# 08_BESIDE_CPU.net
KiCad netlist of a schematic drawn in Altium Designer
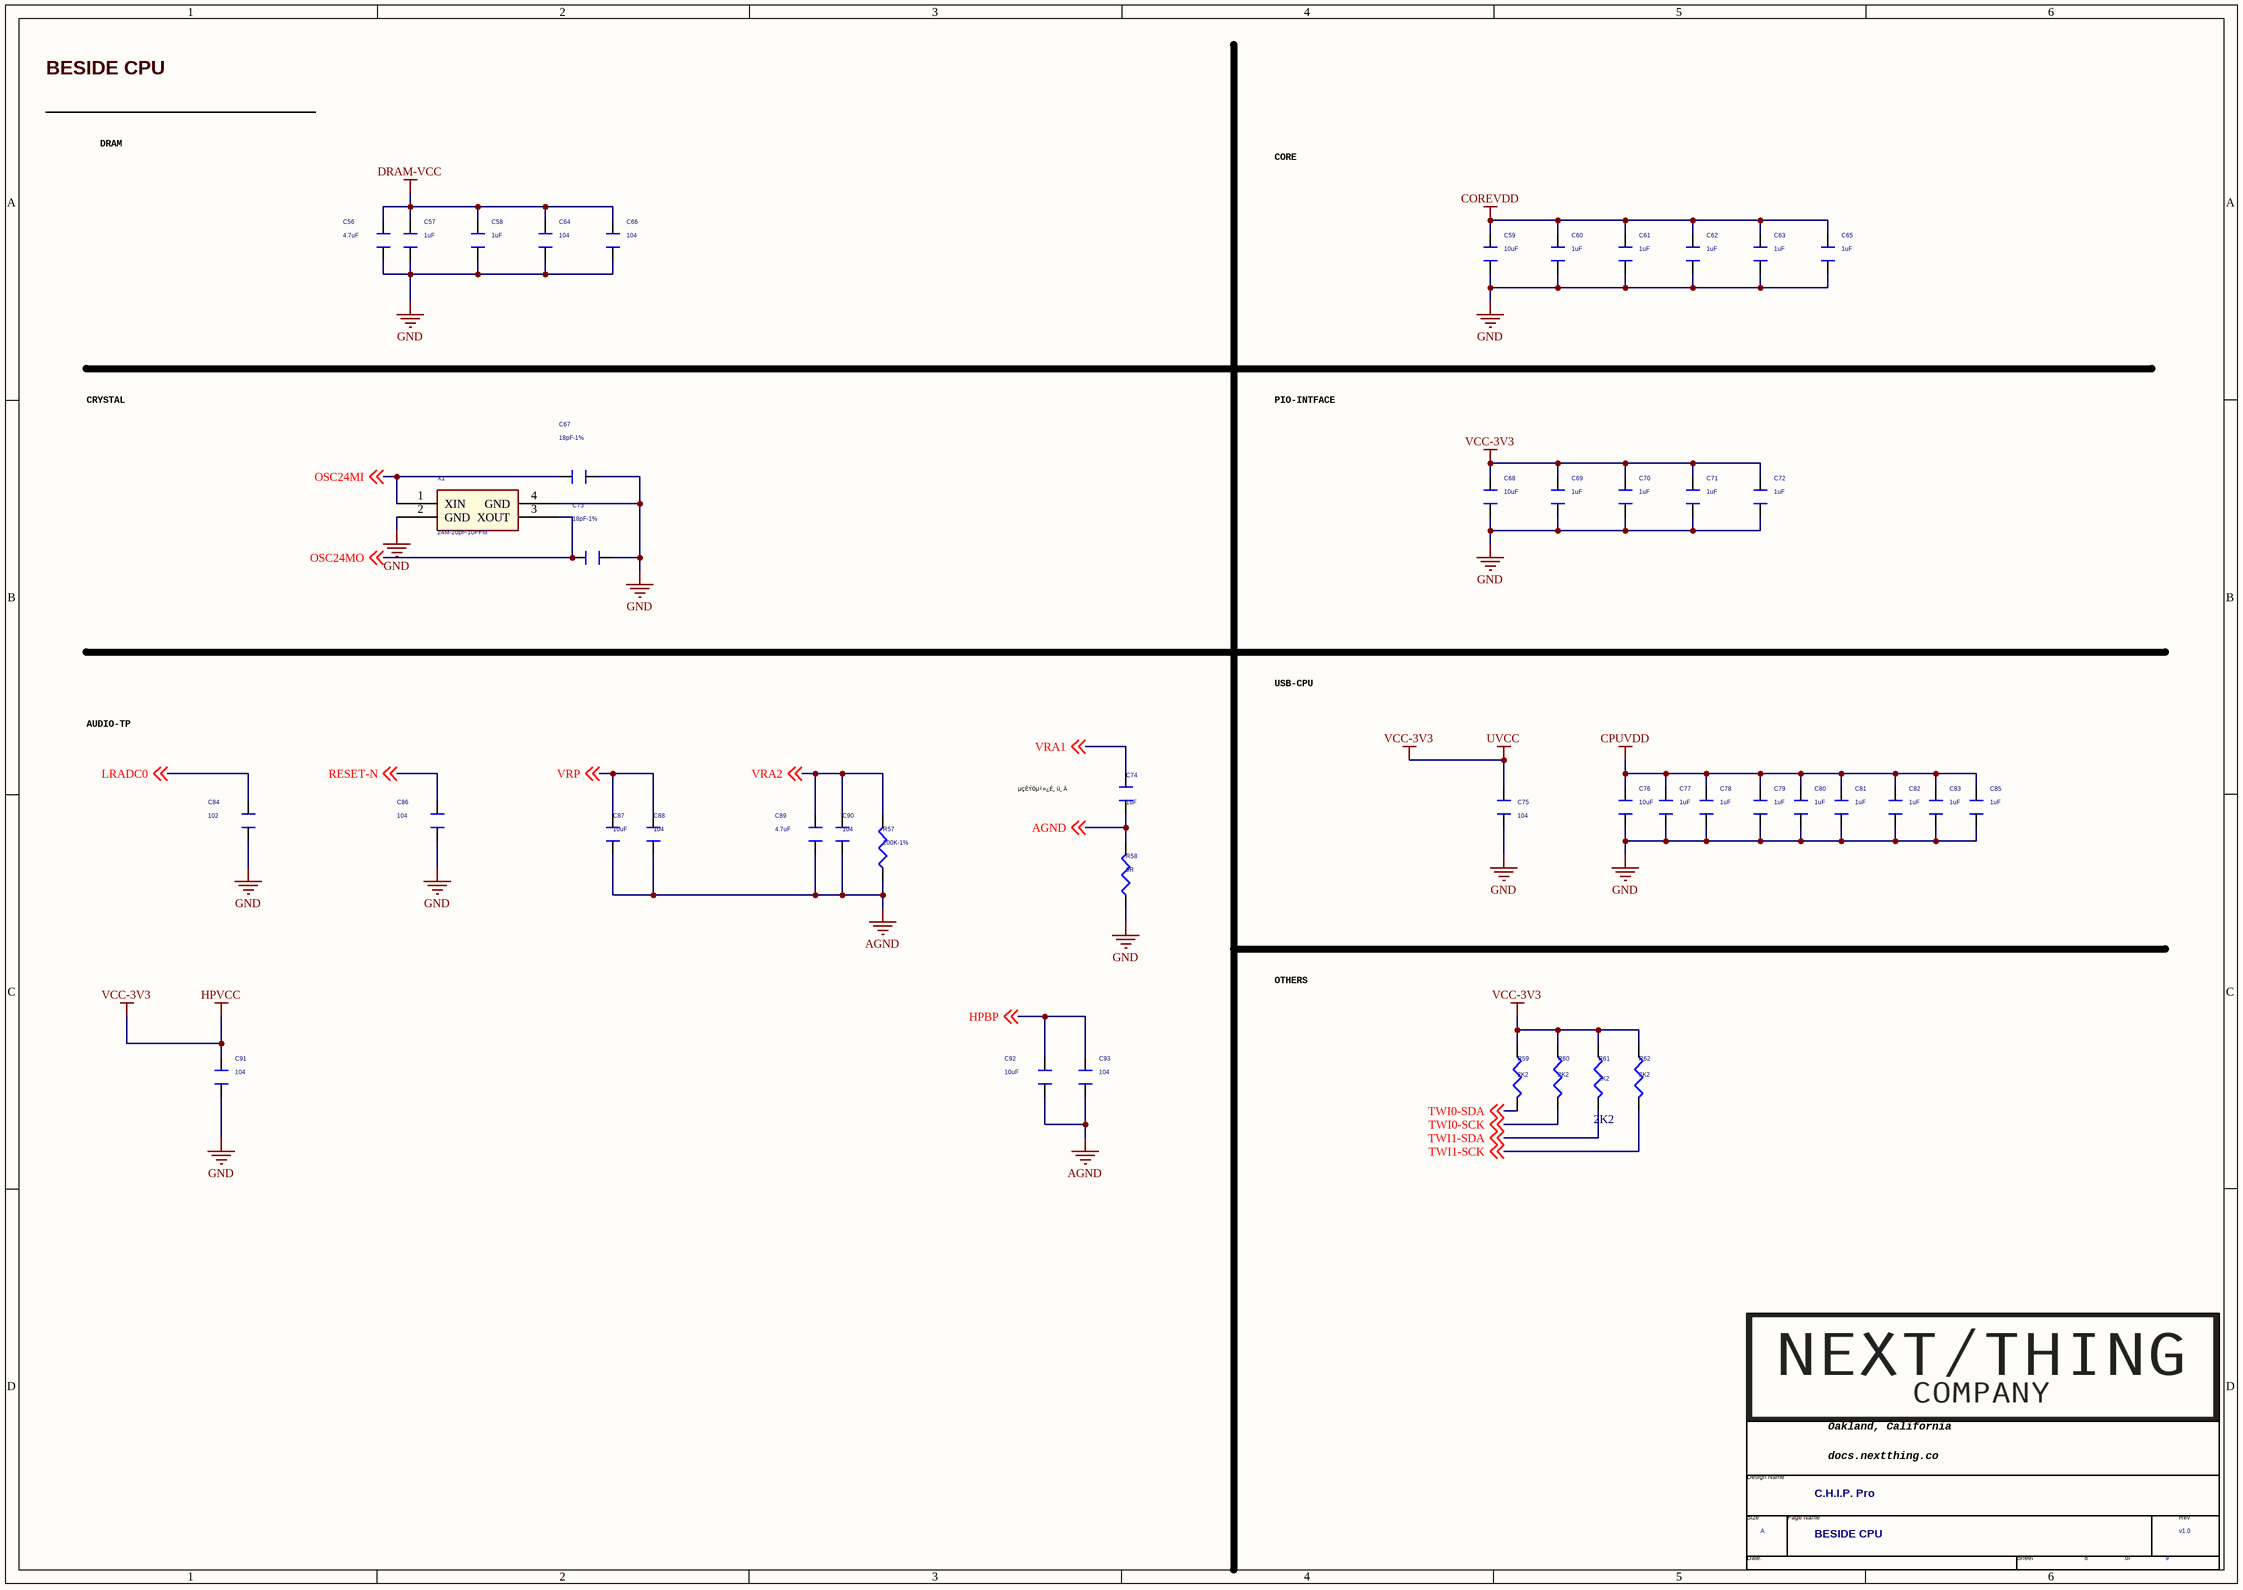
[diagram p0: 08 BESIDE CPU.SchDoc]

(export (version "E")
  (design (tool "Eeschema 10.0.6"))
  (components
    (comp (ref "C56") (value "4.7uF") (footprint "C0603") (libsource (lib "*") (part "CAPACITOR_0_Dup4")))
    (comp (ref "C57") (value "1uF") (footprint "C0402") (libsource (lib "*") (part "CAPACITOR_0_Dup4")))
    (comp (ref "C58") (value "1uF") (footprint "C0402") (libsource (lib "*") (part "CAPACITOR_0_Dup4")))
    (comp (ref "C59") (value "10uF") (footprint "C0603") (libsource (lib "*") (part "CAPACITOR_0_Dup3")))
    (comp (ref "C60") (value "1uF") (footprint "C0402") (libsource (lib "*") (part "CAPACITOR_0_Dup3")))
    (comp (ref "C61") (value "1uF") (footprint "C0402") (libsource (lib "*") (part "CAPACITOR_0_Dup3")))
    (comp (ref "C62") (value "1uF") (footprint "C0402") (libsource (lib "*") (part "CAPACITOR_0_Dup3")))
    (comp (ref "C63") (value "1uF") (footprint "C0402") (libsource (lib "*") (part "CAPACITOR_0_Dup3")))
    (comp (ref "C64") (value "104") (footprint "C0201") (libsource (lib "*") (part "CAPACITOR_0_Dup4")))
    (comp (ref "C65") (value "1uF") (footprint "C0402") (libsource (lib "*") (part "CAPACITOR_0_Dup3")))
    (comp (ref "C66") (value "104") (footprint "C0201") (libsource (lib "*") (part "CAPACITOR_0_Dup4")))
    (comp (ref "C67") (value "18pF-1%") (footprint "C0201") (libsource (lib "*") (part "CAPACITOR_0_Dup4")))
    (comp (ref "C68") (value "10uF") (footprint "C0603") (libsource (lib "*") (part "CAPACITOR_0_Dup3")))
    (comp (ref "C69") (value "1uF") (footprint "C0402") (libsource (lib "*") (part "CAPACITOR_0_Dup4")))
    (comp (ref "C70") (value "1uF") (footprint "C0402") (libsource (lib "*") (part "CAPACITOR_0_Dup4")))
    (comp (ref "C71") (value "1uF") (footprint "C0402") (libsource (lib "*") (part "CAPACITOR_0_Dup4")))
    (comp (ref "C72") (value "1uF") (footprint "C0402") (libsource (lib "*") (part "CAPACITOR_0_Dup4")))
    (comp (ref "C73") (value "18pF-1%") (footprint "C0201") (libsource (lib "*") (part "CAPACITOR_0_Dup4")))
    (comp (ref "C74") (value "1uF") (footprint "C0402") (libsource (lib "*") (part "CAPACITOR_0_Dup4")))
    (comp (ref "C75") (value "104") (footprint "C0201") (libsource (lib "*") (part "CAPACITOR_0_Dup4")))
    (comp (ref "C76") (value "10uF") (footprint "C0603") (libsource (lib "*") (part "CAPACITOR_0_Dup3")))
    (comp (ref "C77") (value "1uF") (footprint "C0402") (libsource (lib "*") (part "CAPACITOR_0_Dup3")))
    (comp (ref "C78") (value "1uF") (footprint "C0402") (libsource (lib "*") (part "CAPACITOR_0_Dup3")))
    (comp (ref "C79") (value "1uF") (footprint "C0402") (libsource (lib "*") (part "CAPACITOR_0_Dup3")))
    (comp (ref "C80") (value "1uF") (footprint "C0402") (libsource (lib "*") (part "CAPACITOR_0_Dup3")))
    (comp (ref "C81") (value "1uF") (footprint "C0402") (libsource (lib "*") (part "CAPACITOR_0_Dup3")))
    (comp (ref "C82") (value "1uF") (footprint "C0402") (libsource (lib "*") (part "CAPACITOR_0_Dup3")))
    (comp (ref "C83") (value "1uF") (footprint "C0402") (libsource (lib "*") (part "CAPACITOR_0_Dup3")))
    (comp (ref "C84") (value "102") (footprint "C0201") (libsource (lib "*") (part "CAPACITOR_0_Dup4")))
    (comp (ref "C85") (value "1uF") (footprint "C0402") (libsource (lib "*") (part "CAPACITOR_0_Dup3")))
    (comp (ref "C86") (value "104") (footprint "C0201") (libsource (lib "*") (part "CAPACITOR_0_Dup4")))
    (comp (ref "C87") (value "10uF") (footprint "C0603") (libsource (lib "*") (part "CAPACITOR_0_Dup4")))
    (comp (ref "C88") (value "104") (footprint "C0201") (libsource (lib "*") (part "CAPACITOR_0_Dup4")))
    (comp (ref "C89") (value "4.7uF") (footprint "C0603") (libsource (lib "*") (part "CAPACITOR_0_Dup4")))
    (comp (ref "C90") (value "104") (footprint "C0201") (libsource (lib "*") (part "CAPACITOR_0_Dup4")))
    (comp (ref "C91") (value "104") (footprint "C0201") (libsource (lib "*") (part "CAPACITOR_0_Dup4")))
    (comp (ref "C92") (value "10uF") (footprint "C0603") (libsource (lib "*") (part "CAPACITOR_0_Dup4")))
    (comp (ref "C93") (value "104") (footprint "C0201") (libsource (lib "*") (part "CAPACITOR_0_Dup4")))
    (comp (ref "R57") (value "200K-1%") (footprint "R0201") (libsource (lib "*") (part "R_Dup2")))
    (comp (ref "R58") (value "0R") (footprint "R0201") (libsource (lib "*") (part "R_Dup2")))
    (comp (ref "R59") (value "2K2") (footprint "R0201") (libsource (lib "*") (part "R_Dup2")))
    (comp (ref "R60") (value "2K2") (footprint "R0201") (libsource (lib "*") (part "R_Dup2")))
    (comp (ref "R61")
      (value "2K2")
      (footprint "R0201")
      (fields (field (name "ALTIUM_VALUE") "2K2"))
      (libsource (lib "*") (part "R_Dup2"))
    )
    (comp (ref "R62") (value "2K2") (footprint "R0201") (libsource (lib "*") (part "R_Dup2")))
    (comp (ref "X1")
      (value "24M-20pF-10PPM")
      (footprint "CRY-3225")
      (description "Crystal 24MHz 20pF 10ppm  -30 to +85")
      (fields (field (name "PART NUMBER") "7M24000004"))
      (libsource (lib "*") (part "CRYSTAL-4_3"))
    )
  )
  (nets
    (net (code "1") (name "AGND") (class "Default")
      (node (ref "C74") (pin "1") (pinfunction "1_1") (pintype "passive"))
      (node (ref "C87") (pin "1") (pinfunction "1_1") (pintype "passive"))
      (node (ref "C88") (pin "1") (pinfunction "1_1") (pintype "passive"))
      (node (ref "C89") (pin "1") (pinfunction "1_1") (pintype "passive"))
      (node (ref "C90") (pin "1") (pinfunction "1_1") (pintype "passive"))
      (node (ref "C92") (pin "1") (pinfunction "1_1") (pintype "passive"))
      (node (ref "C93") (pin "1") (pinfunction "1_1") (pintype "passive"))
      (node (ref "R57") (pin "1") (pinfunction "1_1") (pintype "passive"))
      (node (ref "R58") (pin "2") (pinfunction "2_2") (pintype "passive"))
    )
    (net (code "2") (name "COREVDD") (class "Default")
      (node (ref "C59") (pin "1") (pinfunction "1_1") (pintype "passive"))
      (node (ref "C60") (pin "1") (pinfunction "1_1") (pintype "passive"))
      (node (ref "C61") (pin "1") (pinfunction "1_1") (pintype "passive"))
      (node (ref "C62") (pin "1") (pinfunction "1_1") (pintype "passive"))
      (node (ref "C63") (pin "1") (pinfunction "1_1") (pintype "passive"))
      (node (ref "C65") (pin "1") (pinfunction "1_1") (pintype "passive"))
    )
    (net (code "3") (name "CPUVDD") (class "Default")
      (node (ref "C76") (pin "1") (pinfunction "1_1") (pintype "passive"))
      (node (ref "C77") (pin "1") (pinfunction "1_1") (pintype "passive"))
      (node (ref "C78") (pin "1") (pinfunction "1_1") (pintype "passive"))
      (node (ref "C79") (pin "1") (pinfunction "1_1") (pintype "passive"))
      (node (ref "C80") (pin "1") (pinfunction "1_1") (pintype "passive"))
      (node (ref "C81") (pin "1") (pinfunction "1_1") (pintype "passive"))
      (node (ref "C82") (pin "1") (pinfunction "1_1") (pintype "passive"))
      (node (ref "C83") (pin "1") (pinfunction "1_1") (pintype "passive"))
      (node (ref "C85") (pin "1") (pinfunction "1_1") (pintype "passive"))
    )
    (net (code "4") (name "DRAM-VCC") (class "Default")
      (node (ref "C56") (pin "2") (pinfunction "2_2") (pintype "passive"))
      (node (ref "C57") (pin "2") (pinfunction "2_2") (pintype "passive"))
      (node (ref "C58") (pin "2") (pinfunction "2_2") (pintype "passive"))
      (node (ref "C64") (pin "2") (pinfunction "2_2") (pintype "passive"))
      (node (ref "C66") (pin "2") (pinfunction "2_2") (pintype "passive"))
    )
    (net (code "5") (name "GND") (class "Default")
      (node (ref "C56") (pin "1") (pinfunction "1_1") (pintype "passive"))
      (node (ref "C57") (pin "1") (pinfunction "1_1") (pintype "passive"))
      (node (ref "C58") (pin "1") (pinfunction "1_1") (pintype "passive"))
      (node (ref "C59") (pin "2") (pinfunction "2_2") (pintype "passive"))
      (node (ref "C60") (pin "2") (pinfunction "2_2") (pintype "passive"))
      (node (ref "C61") (pin "2") (pinfunction "2_2") (pintype "passive"))
      (node (ref "C62") (pin "2") (pinfunction "2_2") (pintype "passive"))
      (node (ref "C63") (pin "2") (pinfunction "2_2") (pintype "passive"))
      (node (ref "C64") (pin "1") (pinfunction "1_1") (pintype "passive"))
      (node (ref "C65") (pin "2") (pinfunction "2_2") (pintype "passive"))
      (node (ref "C66") (pin "1") (pinfunction "1_1") (pintype "passive"))
      (node (ref "C67") (pin "1") (pinfunction "1_1") (pintype "passive"))
      (node (ref "C68") (pin "2") (pinfunction "2_2") (pintype "passive"))
      (node (ref "C69") (pin "1") (pinfunction "1_1") (pintype "passive"))
      (node (ref "C70") (pin "1") (pinfunction "1_1") (pintype "passive"))
      (node (ref "C71") (pin "1") (pinfunction "1_1") (pintype "passive"))
      (node (ref "C72") (pin "1") (pinfunction "1_1") (pintype "passive"))
      (node (ref "C73") (pin "1") (pinfunction "1_1") (pintype "passive"))
      (node (ref "C75") (pin "1") (pinfunction "1_1") (pintype "passive"))
      (node (ref "C76") (pin "2") (pinfunction "2_2") (pintype "passive"))
      (node (ref "C77") (pin "2") (pinfunction "2_2") (pintype "passive"))
      (node (ref "C78") (pin "2") (pinfunction "2_2") (pintype "passive"))
      (node (ref "C79") (pin "2") (pinfunction "2_2") (pintype "passive"))
      (node (ref "C80") (pin "2") (pinfunction "2_2") (pintype "passive"))
      (node (ref "C81") (pin "2") (pinfunction "2_2") (pintype "passive"))
      (node (ref "C82") (pin "2") (pinfunction "2_2") (pintype "passive"))
      (node (ref "C83") (pin "2") (pinfunction "2_2") (pintype "passive"))
      (node (ref "C84") (pin "1") (pinfunction "1_1") (pintype "passive"))
      (node (ref "C85") (pin "2") (pinfunction "2_2") (pintype "passive"))
      (node (ref "C86") (pin "1") (pinfunction "1_1") (pintype "passive"))
      (node (ref "C91") (pin "1") (pinfunction "1_1") (pintype "passive"))
      (node (ref "R58") (pin "1") (pinfunction "1_1") (pintype "passive"))
      (node (ref "X1") (pin "2") (pinfunction "GND_2") (pintype "power_in"))
      (node (ref "X1") (pin "4") (pinfunction "GND_4") (pintype "power_in"))
    )
    (net (code "6") (name "HPBP") (class "Default")
      (node (ref "C92") (pin "2") (pinfunction "2_2") (pintype "passive"))
      (node (ref "C93") (pin "2") (pinfunction "2_2") (pintype "passive"))
    )
    (net (code "7") (name "HPVCC") (class "Default")
      (node (ref "C68") (pin "1") (pinfunction "1_1") (pintype "passive"))
      (node (ref "C69") (pin "2") (pinfunction "2_2") (pintype "passive"))
      (node (ref "C70") (pin "2") (pinfunction "2_2") (pintype "passive"))
      (node (ref "C71") (pin "2") (pinfunction "2_2") (pintype "passive"))
      (node (ref "C72") (pin "2") (pinfunction "2_2") (pintype "passive"))
      (node (ref "C75") (pin "2") (pinfunction "2_2") (pintype "passive"))
      (node (ref "C91") (pin "2") (pinfunction "2_2") (pintype "passive"))
      (node (ref "R59") (pin "1") (pinfunction "1_1") (pintype "passive"))
      (node (ref "R60") (pin "1") (pinfunction "1_1") (pintype "passive"))
      (node (ref "R61") (pin "1") (pinfunction "1_1") (pintype "passive"))
      (node (ref "R62") (pin "1") (pinfunction "1_1") (pintype "passive"))
    )
    (net (code "8") (name "LRADC0") (class "Default")
      (node (ref "C84") (pin "2") (pinfunction "2_2") (pintype "passive"))
    )
    (net (code "9") (name "OSC24MI") (class "Default")
      (node (ref "C67") (pin "2") (pinfunction "2_2") (pintype "passive"))
      (node (ref "X1") (pin "1") (pinfunction "XIN_1") (pintype "passive"))
    )
    (net (code "10") (name "OSC24MO") (class "Default")
      (node (ref "C73") (pin "2") (pinfunction "2_2") (pintype "passive"))
      (node (ref "X1") (pin "3") (pinfunction "XOUT_3") (pintype "passive"))
    )
    (net (code "11") (name "RESET-N") (class "Default")
      (node (ref "C86") (pin "2") (pinfunction "2_2") (pintype "passive"))
    )
    (net (code "12") (name "TWI0-SCK") (class "Default")
      (node (ref "R60") (pin "2") (pinfunction "2_2") (pintype "passive"))
    )
    (net (code "13") (name "TWI0-SDA") (class "Default")
      (node (ref "R59") (pin "2") (pinfunction "2_2") (pintype "passive"))
    )
    (net (code "14") (name "TWI1-SCK") (class "Default")
      (node (ref "R62") (pin "2") (pinfunction "2_2") (pintype "passive"))
    )
    (net (code "15") (name "TWI1-SDA") (class "Default")
      (node (ref "R61") (pin "2") (pinfunction "2_2") (pintype "passive"))
    )
    (net (code "16") (name "VRA1") (class "Default")
      (node (ref "C74") (pin "2") (pinfunction "2_2") (pintype "passive"))
    )
    (net (code "17") (name "VRA2") (class "Default")
      (node (ref "C89") (pin "2") (pinfunction "2_2") (pintype "passive"))
      (node (ref "C90") (pin "2") (pinfunction "2_2") (pintype "passive"))
      (node (ref "R57") (pin "2") (pinfunction "2_2") (pintype "passive"))
    )
    (net (code "18") (name "VRP") (class "Default")
      (node (ref "C87") (pin "2") (pinfunction "2_2") (pintype "passive"))
      (node (ref "C88") (pin "2") (pinfunction "2_2") (pintype "passive"))
    )
  )
)
